# ADV7611.net
KiCad netlist of a schematic drawn in Altium Designer
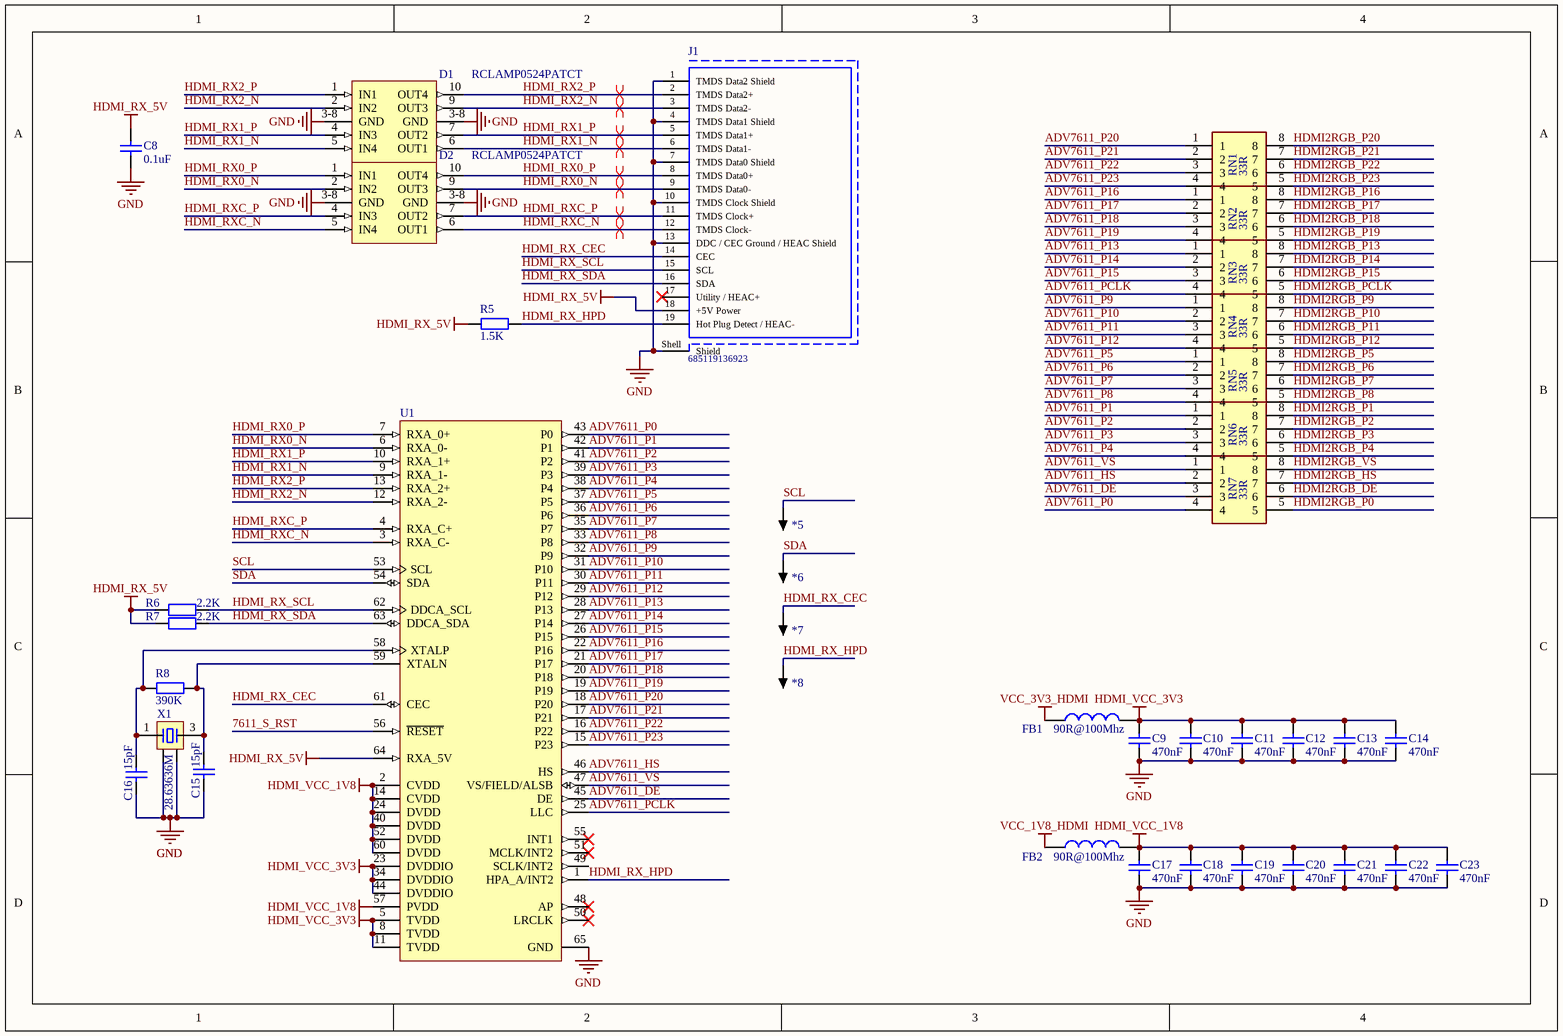
[diagram p0: ADV7611.SchDoc]

(export (version "E")
  (design (tool "Eeschema 10.0.6"))
  (components
    (comp (ref "*5")
      (value "CS")
      (footprint "R100")
      (description "探针焊盘")
      (libsource (lib "0.7 - 常用按键-开关-蜂鸣器-电池-测试点") (part "CS"))
    )
    (comp (ref "*6")
      (value "CS")
      (footprint "R100")
      (description "探针焊盘")
      (libsource (lib "0.7 - 常用按键-开关-蜂鸣器-电池-测试点") (part "CS"))
    )
    (comp (ref "*7")
      (value "CS")
      (footprint "R100")
      (description "探针焊盘")
      (libsource (lib "0.7 - 常用按键-开关-蜂鸣器-电池-测试点") (part "CS"))
    )
    (comp (ref "*8")
      (value "CS")
      (footprint "R100")
      (description "探针焊盘")
      (libsource (lib "0.7 - 常用按键-开关-蜂鸣器-电池-测试点") (part "CS"))
    )
    (comp (ref "C8")
      (value "0.1uF")
      (footprint "C0402_L")
      (description "贴片电容")
      (libsource (lib "0.1 - 电阻-电容-电感-磁珠-电位器") (part "C"))
    )
    (comp (ref "C9")
      (value "470nF")
      (footprint "C0402_L")
      (description "贴片电容")
      (libsource (lib "0.1 - 电阻-电容-电感-磁珠-电位器") (part "C"))
    )
    (comp (ref "C10")
      (value "470nF")
      (footprint "C0402_L")
      (description "贴片电容")
      (libsource (lib "0.1 - 电阻-电容-电感-磁珠-电位器") (part "C"))
    )
    (comp (ref "C11")
      (value "470nF")
      (footprint "C0402_L")
      (description "贴片电容")
      (libsource (lib "0.1 - 电阻-电容-电感-磁珠-电位器") (part "C"))
    )
    (comp (ref "C12")
      (value "470nF")
      (footprint "C0402_L")
      (description "贴片电容")
      (libsource (lib "0.1 - 电阻-电容-电感-磁珠-电位器") (part "C"))
    )
    (comp (ref "C13")
      (value "470nF")
      (footprint "C0402_L")
      (description "贴片电容")
      (libsource (lib "0.1 - 电阻-电容-电感-磁珠-电位器") (part "C"))
    )
    (comp (ref "C14")
      (value "470nF")
      (footprint "C0402_L")
      (description "贴片电容")
      (libsource (lib "0.1 - 电阻-电容-电感-磁珠-电位器") (part "C"))
    )
    (comp (ref "C15")
      (value "15pF")
      (footprint "C0402_L")
      (description "贴片电容")
      (libsource (lib "0.1 - 电阻-电容-电感-磁珠-电位器") (part "C"))
    )
    (comp (ref "C16")
      (value "15pF")
      (footprint "C0402_L")
      (description "贴片电容")
      (libsource (lib "0.1 - 电阻-电容-电感-磁珠-电位器") (part "C"))
    )
    (comp (ref "C17")
      (value "470nF")
      (footprint "C0402_L")
      (description "贴片电容")
      (libsource (lib "0.1 - 电阻-电容-电感-磁珠-电位器") (part "C"))
    )
    (comp (ref "C18")
      (value "470nF")
      (footprint "C0402_L")
      (description "贴片电容")
      (libsource (lib "0.1 - 电阻-电容-电感-磁珠-电位器") (part "C"))
    )
    (comp (ref "C19")
      (value "470nF")
      (footprint "C0402_L")
      (description "贴片电容")
      (libsource (lib "0.1 - 电阻-电容-电感-磁珠-电位器") (part "C"))
    )
    (comp (ref "C20")
      (value "470nF")
      (footprint "C0402_L")
      (description "贴片电容")
      (libsource (lib "0.1 - 电阻-电容-电感-磁珠-电位器") (part "C"))
    )
    (comp (ref "C21")
      (value "470nF")
      (footprint "C0402_L")
      (description "贴片电容")
      (libsource (lib "0.1 - 电阻-电容-电感-磁珠-电位器") (part "C"))
    )
    (comp (ref "C22")
      (value "470nF")
      (footprint "C0402_L")
      (description "贴片电容")
      (libsource (lib "0.1 - 电阻-电容-电感-磁珠-电位器") (part "C"))
    )
    (comp (ref "C23")
      (value "470nF")
      (footprint "C0402_L")
      (description "贴片电容")
      (libsource (lib "0.1 - 电阻-电容-电感-磁珠-电位器") (part "C"))
    )
    (comp (ref "D1")
      (value "RCLAMP0524PATCT")
      (footprint "FP-SLP2510P8-MFG")
      (description "TVS DIODE 5V 15V SLP2510P8")
      (libsource (lib "AD") (part "RCLAMP0524PATCT"))
    )
    (comp (ref "D2")
      (value "RCLAMP0524PATCT")
      (footprint "FP-SLP2510P8-MFG")
      (description "TVS DIODE 5V 15V SLP2510P8")
      (libsource (lib "AD") (part "RCLAMP0524PATCT"))
    )
    (comp (ref "FB1")
      (value "90R@100Mhz")
      (footprint "L0402")
      (description "磁珠")
      (libsource (lib "0.1 - 电阻-电容-电感-磁珠-电位器") (part "L"))
    )
    (comp (ref "FB2")
      (value "90R@100Mhz")
      (footprint "L0402")
      (description "磁珠")
      (libsource (lib "0.1 - 电阻-电容-电感-磁珠-电位器") (part "L"))
    )
    (comp (ref "J1")
      (value "685119136923")
      (footprint "685119136923")
      (description "Mini HDMI Type C Receptacle WR-COM, Horizontal, SMT")
      (fields (field (name "MANUFACTURER") "Wurth Elektronik") (field (name "PUBLISHER") "WurthElektronik"))
      (libsource (lib "Components - 25.06.23 - 21.10") (part "CMP-1502-00171-1"))
    )
    (comp (ref "R5")
      (value "1.5K")
      (footprint "R0402_L")
      (description "贴片电阻")
      (libsource (lib "0.1 - 电阻-电容-电感-磁珠-电位器") (part "R"))
    )
    (comp (ref "R6")
      (value "2.2K")
      (footprint "R0402_L")
      (description "贴片电阻")
      (libsource (lib "0.1 - 电阻-电容-电感-磁珠-电位器") (part "R"))
    )
    (comp (ref "R7")
      (value "2.2K")
      (footprint "R0402_L")
      (description "贴片电阻")
      (libsource (lib "0.1 - 电阻-电容-电感-磁珠-电位器") (part "R"))
    )
    (comp (ref "R8")
      (value "390K")
      (footprint "R0402_L")
      (description "贴片电阻")
      (libsource (lib "0.1 - 电阻-电容-电感-磁珠-电位器") (part "R"))
    )
    (comp (ref "RN1")
      (value "33R")
      (footprint "SamacSys:EXB28V510JX")
      (description "Resistor Network")
      (fields
        (field (name "MANUFACTURER_PART_NUMBER") "EXB-28V330JX")
        (field (name "MOUSER PART NUMBER") "667-EXB-28V330JX")
      )
      (libsource (lib "SamacSys") (part "0804"))
    )
    (comp (ref "RN2")
      (value "33R")
      (footprint "SamacSys:EXB28V510JX")
      (description "Resistor Network")
      (fields
        (field (name "MANUFACTURER_PART_NUMBER") "EXB-28V330JX")
        (field (name "MOUSER PART NUMBER") "667-EXB-28V330JX")
      )
      (libsource (lib "SamacSys") (part "0804"))
    )
    (comp (ref "RN3")
      (value "33R")
      (footprint "SamacSys:EXB28V510JX")
      (description "Resistor Network")
      (fields
        (field (name "MANUFACTURER_PART_NUMBER") "EXB-28V330JX")
        (field (name "MOUSER PART NUMBER") "667-EXB-28V330JX")
      )
      (libsource (lib "SamacSys") (part "0804"))
    )
    (comp (ref "RN4")
      (value "33R")
      (footprint "SamacSys:EXB28V510JX")
      (description "Resistor Network")
      (fields
        (field (name "MANUFACTURER_PART_NUMBER") "EXB-28V330JX")
        (field (name "MOUSER PART NUMBER") "667-EXB-28V330JX")
      )
      (libsource (lib "SamacSys") (part "0804"))
    )
    (comp (ref "RN5")
      (value "33R")
      (footprint "SamacSys:EXB28V510JX")
      (description "Resistor Network")
      (fields
        (field (name "MANUFACTURER_PART_NUMBER") "EXB-28V330JX")
        (field (name "MOUSER PART NUMBER") "667-EXB-28V330JX")
      )
      (libsource (lib "SamacSys") (part "0804"))
    )
    (comp (ref "RN6")
      (value "33R")
      (footprint "SamacSys:EXB28V510JX")
      (description "Resistor Network")
      (fields
        (field (name "MANUFACTURER_PART_NUMBER") "EXB-28V330JX")
        (field (name "MOUSER PART NUMBER") "667-EXB-28V330JX")
      )
      (libsource (lib "SamacSys") (part "0804"))
    )
    (comp (ref "RN7")
      (value "33R")
      (footprint "SamacSys:EXB28V510JX")
      (description "Resistor Network")
      (fields
        (field (name "MANUFACTURER_PART_NUMBER") "EXB-28V330JX")
        (field (name "MOUSER PART NUMBER") "667-EXB-28V330JX")
      )
      (libsource (lib "SamacSys") (part "0804"))
    )
    (comp (ref "U1")
      (value "~")
      (footprint "ADI-SW-64-2_L")
      (fields (field (name "MANUFACTURER") "Analog Devices") (field (name "PARTNUMBER") "ADV7611BSWZ-P"))
      (libsource (lib "Components - 25.06.23 - 21.52") (part "CMP-1517-00002-1"))
    )
    (comp (ref "X1")
      (value "28.63636M")
      (footprint "OSC 3225-4P")
      (description "4脚无源晶振")
      (libsource (lib "0.5 - 保险丝-晶振-光耦") (part "XTAL-4P"))
    )
  )
  (nets
    (net (code "1") (name "/7611_S_RST") (class "Default")
      (node (ref "U1") (pin "56") (pinfunction "~{RESET}_56") (pintype "input"))
    )
    (net (code "2") (name "/ADV7611_DE") (class "Default")
      (node (ref "RN7") (pin "3") (pinfunction "3_3") (pintype "passive"))
      (node (ref "U1") (pin "45") (pinfunction "DE_45") (pintype "output"))
    )
    (net (code "3") (name "/ADV7611_HS") (class "Default")
      (node (ref "RN7") (pin "2") (pinfunction "2_2") (pintype "passive"))
      (node (ref "U1") (pin "46") (pinfunction "HS_46") (pintype "output"))
    )
    (net (code "4") (name "/ADV7611_P0") (class "Default")
      (node (ref "RN7") (pin "4") (pinfunction "4_4") (pintype "passive"))
      (node (ref "U1") (pin "43") (pinfunction "P0_43") (pintype "output"))
    )
    (net (code "5") (name "/ADV7611_P1") (class "Default")
      (node (ref "RN6") (pin "1") (pinfunction "1_1") (pintype "passive"))
      (node (ref "U1") (pin "42") (pinfunction "P1_42") (pintype "output"))
    )
    (net (code "6") (name "/ADV7611_P2") (class "Default")
      (node (ref "RN6") (pin "2") (pinfunction "2_2") (pintype "passive"))
      (node (ref "U1") (pin "41") (pinfunction "P2_41") (pintype "output"))
    )
    (net (code "7") (name "/ADV7611_P3") (class "Default")
      (node (ref "RN6") (pin "3") (pinfunction "3_3") (pintype "passive"))
      (node (ref "U1") (pin "39") (pinfunction "P3_39") (pintype "output"))
    )
    (net (code "8") (name "/ADV7611_P4") (class "Default")
      (node (ref "RN6") (pin "4") (pinfunction "4_4") (pintype "passive"))
      (node (ref "U1") (pin "38") (pinfunction "P4_38") (pintype "output"))
    )
    (net (code "9") (name "/ADV7611_P5") (class "Default")
      (node (ref "RN5") (pin "1") (pinfunction "1_1") (pintype "passive"))
      (node (ref "U1") (pin "37") (pinfunction "P5_37") (pintype "output"))
    )
    (net (code "10") (name "/ADV7611_P6") (class "Default")
      (node (ref "RN5") (pin "2") (pinfunction "2_2") (pintype "passive"))
      (node (ref "U1") (pin "36") (pinfunction "P6_36") (pintype "output"))
    )
    (net (code "11") (name "/ADV7611_P7") (class "Default")
      (node (ref "RN5") (pin "3") (pinfunction "3_3") (pintype "passive"))
      (node (ref "U1") (pin "35") (pinfunction "P7_35") (pintype "output"))
    )
    (net (code "12") (name "/ADV7611_P8") (class "Default")
      (node (ref "RN5") (pin "4") (pinfunction "4_4") (pintype "passive"))
      (node (ref "U1") (pin "33") (pinfunction "P8_33") (pintype "output"))
    )
    (net (code "13") (name "/ADV7611_P9") (class "Default")
      (node (ref "RN4") (pin "1") (pinfunction "1_1") (pintype "passive"))
      (node (ref "U1") (pin "32") (pinfunction "P9_32") (pintype "output"))
    )
    (net (code "14") (name "/ADV7611_P10") (class "Default")
      (node (ref "RN4") (pin "2") (pinfunction "2_2") (pintype "passive"))
      (node (ref "U1") (pin "31") (pinfunction "P10_31") (pintype "output"))
    )
    (net (code "15") (name "/ADV7611_P11") (class "Default")
      (node (ref "RN4") (pin "3") (pinfunction "3_3") (pintype "passive"))
      (node (ref "U1") (pin "30") (pinfunction "P11_30") (pintype "output"))
    )
    (net (code "16") (name "/ADV7611_P12") (class "Default")
      (node (ref "RN4") (pin "4") (pinfunction "4_4") (pintype "passive"))
      (node (ref "U1") (pin "29") (pinfunction "P12_29") (pintype "output"))
    )
    (net (code "17") (name "/ADV7611_P13") (class "Default")
      (node (ref "RN3") (pin "1") (pinfunction "1_1") (pintype "passive"))
      (node (ref "U1") (pin "28") (pinfunction "P13_28") (pintype "output"))
    )
    (net (code "18") (name "/ADV7611_P14") (class "Default")
      (node (ref "RN3") (pin "2") (pinfunction "2_2") (pintype "passive"))
      (node (ref "U1") (pin "27") (pinfunction "P14_27") (pintype "output"))
    )
    (net (code "19") (name "/ADV7611_P15") (class "Default")
      (node (ref "RN3") (pin "3") (pinfunction "3_3") (pintype "passive"))
      (node (ref "U1") (pin "26") (pinfunction "P15_26") (pintype "output"))
    )
    (net (code "20") (name "/ADV7611_P16") (class "Default")
      (node (ref "RN2") (pin "1") (pinfunction "1_1") (pintype "passive"))
      (node (ref "U1") (pin "22") (pinfunction "P16_22") (pintype "output"))
    )
    (net (code "21") (name "/ADV7611_P17") (class "Default")
      (node (ref "RN2") (pin "2") (pinfunction "2_2") (pintype "passive"))
      (node (ref "U1") (pin "21") (pinfunction "P17_21") (pintype "output"))
    )
    (net (code "22") (name "/ADV7611_P18") (class "Default")
      (node (ref "RN2") (pin "3") (pinfunction "3_3") (pintype "passive"))
      (node (ref "U1") (pin "20") (pinfunction "P18_20") (pintype "output"))
    )
    (net (code "23") (name "/ADV7611_P19") (class "Default")
      (node (ref "RN2") (pin "4") (pinfunction "4_4") (pintype "passive"))
      (node (ref "U1") (pin "19") (pinfunction "P19_19") (pintype "output"))
    )
    (net (code "24") (name "/ADV7611_P20") (class "Default")
      (node (ref "RN1") (pin "1") (pinfunction "1_1") (pintype "passive"))
      (node (ref "U1") (pin "18") (pinfunction "P20_18") (pintype "output"))
    )
    (net (code "25") (name "/ADV7611_P21") (class "Default")
      (node (ref "RN1") (pin "2") (pinfunction "2_2") (pintype "passive"))
      (node (ref "U1") (pin "17") (pinfunction "P21_17") (pintype "output"))
    )
    (net (code "26") (name "/ADV7611_P22") (class "Default")
      (node (ref "RN1") (pin "3") (pinfunction "3_3") (pintype "passive"))
      (node (ref "U1") (pin "16") (pinfunction "P22_16") (pintype "output"))
    )
    (net (code "27") (name "/ADV7611_P23") (class "Default")
      (node (ref "RN1") (pin "4") (pinfunction "4_4") (pintype "passive"))
      (node (ref "U1") (pin "15") (pinfunction "P23_15") (pintype "output"))
    )
    (net (code "28") (name "/ADV7611_PCLK") (class "Default")
      (node (ref "RN3") (pin "4") (pinfunction "4_4") (pintype "passive"))
      (node (ref "U1") (pin "25") (pinfunction "LLC_25") (pintype "output"))
    )
    (net (code "29") (name "/ADV7611_VS") (class "Default")
      (node (ref "RN7") (pin "1") (pinfunction "1_1") (pintype "passive"))
      (node (ref "U1") (pin "47") (pinfunction "VS/FIELD/ALSB_47") (pintype "bidirectional"))
    )
    (net (code "30") (name "/HDMI2RGB_DE") (class "Default")
      (node (ref "RN7") (pin "6") (pinfunction "6_6") (pintype "passive"))
    )
    (net (code "31") (name "/HDMI2RGB_HS") (class "Default")
      (node (ref "RN7") (pin "7") (pinfunction "7_7") (pintype "passive"))
    )
    (net (code "32") (name "/HDMI2RGB_P0") (class "Default")
      (node (ref "RN7") (pin "5") (pinfunction "5_5") (pintype "passive"))
    )
    (net (code "33") (name "/HDMI2RGB_P1") (class "Default")
      (node (ref "RN6") (pin "8") (pinfunction "8_8") (pintype "passive"))
    )
    (net (code "34") (name "/HDMI2RGB_P2") (class "Default")
      (node (ref "RN6") (pin "7") (pinfunction "7_7") (pintype "passive"))
    )
    (net (code "35") (name "/HDMI2RGB_P3") (class "Default")
      (node (ref "RN6") (pin "6") (pinfunction "6_6") (pintype "passive"))
    )
    (net (code "36") (name "/HDMI2RGB_P4") (class "Default")
      (node (ref "RN6") (pin "5") (pinfunction "5_5") (pintype "passive"))
    )
    (net (code "37") (name "/HDMI2RGB_P5") (class "Default")
      (node (ref "RN5") (pin "8") (pinfunction "8_8") (pintype "passive"))
    )
    (net (code "38") (name "/HDMI2RGB_P6") (class "Default")
      (node (ref "RN5") (pin "7") (pinfunction "7_7") (pintype "passive"))
    )
    (net (code "39") (name "/HDMI2RGB_P7") (class "Default")
      (node (ref "RN5") (pin "6") (pinfunction "6_6") (pintype "passive"))
    )
    (net (code "40") (name "/HDMI2RGB_P8") (class "Default")
      (node (ref "RN5") (pin "5") (pinfunction "5_5") (pintype "passive"))
    )
    (net (code "41") (name "/HDMI2RGB_P9") (class "Default")
      (node (ref "RN4") (pin "8") (pinfunction "8_8") (pintype "passive"))
    )
    (net (code "42") (name "/HDMI2RGB_P10") (class "Default")
      (node (ref "RN4") (pin "7") (pinfunction "7_7") (pintype "passive"))
    )
    (net (code "43") (name "/HDMI2RGB_P11") (class "Default")
      (node (ref "RN4") (pin "6") (pinfunction "6_6") (pintype "passive"))
    )
    (net (code "44") (name "/HDMI2RGB_P12") (class "Default")
      (node (ref "RN4") (pin "5") (pinfunction "5_5") (pintype "passive"))
    )
    (net (code "45") (name "/HDMI2RGB_P13") (class "Default")
      (node (ref "RN3") (pin "8") (pinfunction "8_8") (pintype "passive"))
    )
    (net (code "46") (name "/HDMI2RGB_P14") (class "Default")
      (node (ref "RN3") (pin "7") (pinfunction "7_7") (pintype "passive"))
    )
    (net (code "47") (name "/HDMI2RGB_P15") (class "Default")
      (node (ref "RN3") (pin "6") (pinfunction "6_6") (pintype "passive"))
    )
    (net (code "48") (name "/HDMI2RGB_P16") (class "Default")
      (node (ref "RN2") (pin "8") (pinfunction "8_8") (pintype "passive"))
    )
    (net (code "49") (name "/HDMI2RGB_P17") (class "Default")
      (node (ref "RN2") (pin "7") (pinfunction "7_7") (pintype "passive"))
    )
    (net (code "50") (name "/HDMI2RGB_P18") (class "Default")
      (node (ref "RN2") (pin "6") (pinfunction "6_6") (pintype "passive"))
    )
    (net (code "51") (name "/HDMI2RGB_P19") (class "Default")
      (node (ref "RN2") (pin "5") (pinfunction "5_5") (pintype "passive"))
    )
    (net (code "52") (name "/HDMI2RGB_P20") (class "Default")
      (node (ref "RN1") (pin "8") (pinfunction "8_8") (pintype "passive"))
    )
    (net (code "53") (name "/HDMI2RGB_P21") (class "Default")
      (node (ref "RN1") (pin "7") (pinfunction "7_7") (pintype "passive"))
    )
    (net (code "54") (name "/HDMI2RGB_P22") (class "Default")
      (node (ref "RN1") (pin "6") (pinfunction "6_6") (pintype "passive"))
    )
    (net (code "55") (name "/HDMI2RGB_P23") (class "Default")
      (node (ref "RN1") (pin "5") (pinfunction "5_5") (pintype "passive"))
    )
    (net (code "56") (name "/HDMI2RGB_PCLK") (class "Default")
      (node (ref "RN3") (pin "5") (pinfunction "5_5") (pintype "passive"))
    )
    (net (code "57") (name "/HDMI2RGB_VS") (class "Default")
      (node (ref "RN7") (pin "8") (pinfunction "8_8") (pintype "passive"))
    )
    (net (code "58") (name "/HDMI_RX0_N") (class "Default")
      (node (ref "D2") (pin "2") (pinfunction "IN2_2") (pintype "input"))
      (node (ref "D2") (pin "9") (pinfunction "OUT3_9") (pintype "output"))
      (node (ref "J1") (pin "9") (pinfunction "TMDS_Data0-_9") (pintype "passive"))
      (node (ref "U1") (pin "6") (pinfunction "RXA_0-_6") (pintype "input"))
    )
    (net (code "59") (name "/HDMI_RX0_P") (class "Default")
      (node (ref "D2") (pin "1") (pinfunction "IN1_1") (pintype "input"))
      (node (ref "D2") (pin "10") (pinfunction "OUT4_10") (pintype "output"))
      (node (ref "J1") (pin "8") (pinfunction "TMDS_Data0+_8") (pintype "passive"))
      (node (ref "U1") (pin "7") (pinfunction "RXA_0+_7") (pintype "input"))
    )
    (net (code "60") (name "/HDMI_RX1_N") (class "Default")
      (node (ref "D1") (pin "5") (pinfunction "IN4_5") (pintype "input"))
      (node (ref "D1") (pin "6") (pinfunction "OUT1_6") (pintype "output"))
      (node (ref "J1") (pin "6") (pinfunction "TMDS_Data1-_6") (pintype "passive"))
      (node (ref "U1") (pin "9") (pinfunction "RXA_1-_9") (pintype "input"))
    )
    (net (code "61") (name "/HDMI_RX1_P") (class "Default")
      (node (ref "D1") (pin "4") (pinfunction "IN3_4") (pintype "input"))
      (node (ref "D1") (pin "7") (pinfunction "OUT2_7") (pintype "output"))
      (node (ref "J1") (pin "5") (pinfunction "TMDS_Data1+_5") (pintype "passive"))
      (node (ref "U1") (pin "10") (pinfunction "RXA_1+_10") (pintype "input"))
    )
    (net (code "62") (name "/HDMI_RX2_N") (class "Default")
      (node (ref "D1") (pin "2") (pinfunction "IN2_2") (pintype "input"))
      (node (ref "D1") (pin "9") (pinfunction "OUT3_9") (pintype "output"))
      (node (ref "J1") (pin "3") (pinfunction "TMDS_Data2-_3") (pintype "passive"))
      (node (ref "U1") (pin "12") (pinfunction "RXA_2-_12") (pintype "input"))
    )
    (net (code "63") (name "/HDMI_RX2_P") (class "Default")
      (node (ref "D1") (pin "1") (pinfunction "IN1_1") (pintype "input"))
      (node (ref "D1") (pin "10") (pinfunction "OUT4_10") (pintype "output"))
      (node (ref "J1") (pin "2") (pinfunction "TMDS_Data2+_2") (pintype "passive"))
      (node (ref "U1") (pin "13") (pinfunction "RXA_2+_13") (pintype "input"))
    )
    (net (code "64") (name "/HDMI_RXC_N") (class "Default")
      (node (ref "D2") (pin "5") (pinfunction "IN4_5") (pintype "input"))
      (node (ref "D2") (pin "6") (pinfunction "OUT1_6") (pintype "output"))
      (node (ref "J1") (pin "12") (pinfunction "TMDS_Clock-_12") (pintype "passive"))
      (node (ref "U1") (pin "3") (pinfunction "RXA_C-_3") (pintype "input"))
    )
    (net (code "65") (name "/HDMI_RXC_P") (class "Default")
      (node (ref "D2") (pin "4") (pinfunction "IN3_4") (pintype "input"))
      (node (ref "D2") (pin "7") (pinfunction "OUT2_7") (pintype "output"))
      (node (ref "J1") (pin "11") (pinfunction "TMDS_Clock+_11") (pintype "passive"))
      (node (ref "U1") (pin "4") (pinfunction "RXA_C+_4") (pintype "input"))
    )
    (net (code "66") (name "/HDMI_RX_CEC") (class "Default")
      (node (ref "*7") (pin "1") (pinfunction "1_1") (pintype "passive"))
      (node (ref "J1") (pin "14") (pinfunction "CEC_14") (pintype "passive"))
      (node (ref "U1") (pin "61") (pinfunction "CEC_61") (pintype "bidirectional"))
    )
    (net (code "67") (name "/HDMI_RX_HPD") (class "Default")
      (node (ref "*8") (pin "1") (pinfunction "1_1") (pintype "passive"))
      (node (ref "J1") (pin "19") (pinfunction "Hot_Plug_Detect_/_HEAC-_19") (pintype "passive"))
      (node (ref "R5") (pin "1") (pinfunction "1_1") (pintype "passive"))
      (node (ref "U1") (pin "1") (pinfunction "HPA_A/INT2_1") (pintype "output"))
    )
    (net (code "68") (name "/HDMI_RX_SCL") (class "Default")
      (node (ref "J1") (pin "15") (pinfunction "SCL_15") (pintype "passive"))
      (node (ref "R6") (pin "1") (pinfunction "1_1") (pintype "passive"))
      (node (ref "U1") (pin "62") (pinfunction "DDCA_SCL_62") (pintype "input"))
    )
    (net (code "69") (name "/HDMI_RX_SDA") (class "Default")
      (node (ref "J1") (pin "16") (pinfunction "SDA_16") (pintype "passive"))
      (node (ref "R7") (pin "1") (pinfunction "1_1") (pintype "passive"))
      (node (ref "U1") (pin "63") (pinfunction "DDCA_SDA_63") (pintype "bidirectional"))
    )
    (net (code "70") (name "/SCL") (class "Default")
      (node (ref "*5") (pin "1") (pinfunction "1_1") (pintype "passive"))
      (node (ref "U1") (pin "53") (pinfunction "SCL_53") (pintype "input"))
    )
    (net (code "71") (name "/SDA") (class "Default")
      (node (ref "*6") (pin "1") (pinfunction "1_1") (pintype "passive"))
      (node (ref "U1") (pin "54") (pinfunction "SDA_54") (pintype "bidirectional"))
    )
    (net (code "72") (name "GND") (class "Default")
      (node (ref "C10") (pin "1") (pinfunction "1_1") (pintype "passive"))
      (node (ref "C11") (pin "1") (pinfunction "1_1") (pintype "passive"))
      (node (ref "C12") (pin "1") (pinfunction "1_1") (pintype "passive"))
      (node (ref "C13") (pin "1") (pinfunction "1_1") (pintype "passive"))
      (node (ref "C14") (pin "1") (pinfunction "1_1") (pintype "passive"))
      (node (ref "C15") (pin "2") (pinfunction "2_2") (pintype "passive"))
      (node (ref "C16") (pin "2") (pinfunction "2_2") (pintype "passive"))
      (node (ref "C17") (pin "1") (pinfunction "1_1") (pintype "passive"))
      (node (ref "C18") (pin "1") (pinfunction "1_1") (pintype "passive"))
      (node (ref "C19") (pin "1") (pinfunction "1_1") (pintype "passive"))
      (node (ref "C20") (pin "1") (pinfunction "1_1") (pintype "passive"))
      (node (ref "C21") (pin "1") (pinfunction "1_1") (pintype "passive"))
      (node (ref "C22") (pin "1") (pinfunction "1_1") (pintype "passive"))
      (node (ref "C23") (pin "1") (pinfunction "1_1") (pintype "passive"))
      (node (ref "C8") (pin "1") (pinfunction "1_1") (pintype "passive"))
      (node (ref "C9") (pin "1") (pinfunction "1_1") (pintype "passive"))
      (node (ref "D1") (pin "3-8") (pinfunction "GND_3-8") (pintype "tri_state"))
      (node (ref "D2") (pin "3-8") (pinfunction "GND_3-8") (pintype "tri_state"))
      (node (ref "J1") (pin "1") (pinfunction "TMDS_Data2_Shield_1") (pintype "passive"))
      (node (ref "J1") (pin "10") (pinfunction "TMDS_Clock_Shield_10") (pintype "passive"))
      (node (ref "J1") (pin "13") (pinfunction "DDC_/_CEC_Ground_/_HEAC_Shield_13") (pintype "passive"))
      (node (ref "J1") (pin "4") (pinfunction "TMDS_Data1_Shield_4") (pintype "passive"))
      (node (ref "J1") (pin "7") (pinfunction "TMDS_Data0_Shield_7") (pintype "passive"))
      (node (ref "J1") (pin "Shell") (pinfunction "Shield_Shell") (pintype "passive"))
      (node (ref "U1") (pin "65") (pinfunction "GND_65") (pintype "power_in"))
      (node (ref "X1") (pin "2") (pinfunction "2_2") (pintype "passive"))
      (node (ref "X1") (pin "4") (pinfunction "4_4") (pintype "passive"))
    )
    (net (code "73") (name "HDMI_RX_5V") (class "Default")
      (node (ref "C8") (pin "2") (pinfunction "2_2") (pintype "passive"))
      (node (ref "J1") (pin "18") (pinfunction "+5V_Power_18") (pintype "passive"))
      (node (ref "R5") (pin "2") (pinfunction "2_2") (pintype "passive"))
      (node (ref "R6") (pin "2") (pinfunction "2_2") (pintype "passive"))
      (node (ref "R7") (pin "2") (pinfunction "2_2") (pintype "passive"))
      (node (ref "U1") (pin "64") (pinfunction "RXA_5V_64") (pintype "input"))
    )
    (net (code "74") (name "HDMI_VCC_1V8") (class "Default")
      (node (ref "C17") (pin "2") (pinfunction "2_2") (pintype "passive"))
      (node (ref "C18") (pin "2") (pinfunction "2_2") (pintype "passive"))
      (node (ref "C19") (pin "2") (pinfunction "2_2") (pintype "passive"))
      (node (ref "C20") (pin "2") (pinfunction "2_2") (pintype "passive"))
      (node (ref "C21") (pin "2") (pinfunction "2_2") (pintype "passive"))
      (node (ref "C22") (pin "2") (pinfunction "2_2") (pintype "passive"))
      (node (ref "C23") (pin "2") (pinfunction "2_2") (pintype "passive"))
      (node (ref "FB2") (pin "2") (pinfunction "2_2") (pintype "passive"))
      (node (ref "U1") (pin "14") (pinfunction "CVDD_14") (pintype "power_in"))
      (node (ref "U1") (pin "2") (pinfunction "CVDD_2") (pintype "power_in"))
      (node (ref "U1") (pin "24") (pinfunction "DVDD_24") (pintype "power_in"))
      (node (ref "U1") (pin "40") (pinfunction "DVDD_40") (pintype "power_in"))
      (node (ref "U1") (pin "52") (pinfunction "DVDD_52") (pintype "power_in"))
      (node (ref "U1") (pin "57") (pinfunction "PVDD_57") (pintype "power_in"))
      (node (ref "U1") (pin "60") (pinfunction "DVDD_60") (pintype "power_in"))
    )
    (net (code "75") (name "HDMI_VCC_3V3") (class "Default")
      (node (ref "C10") (pin "2") (pinfunction "2_2") (pintype "passive"))
      (node (ref "C11") (pin "2") (pinfunction "2_2") (pintype "passive"))
      (node (ref "C12") (pin "2") (pinfunction "2_2") (pintype "passive"))
      (node (ref "C13") (pin "2") (pinfunction "2_2") (pintype "passive"))
      (node (ref "C14") (pin "2") (pinfunction "2_2") (pintype "passive"))
      (node (ref "C9") (pin "2") (pinfunction "2_2") (pintype "passive"))
      (node (ref "FB1") (pin "2") (pinfunction "2_2") (pintype "passive"))
      (node (ref "U1") (pin "11") (pinfunction "TVDD_11") (pintype "power_in"))
      (node (ref "U1") (pin "23") (pinfunction "DVDDIO_23") (pintype "power_in"))
      (node (ref "U1") (pin "34") (pinfunction "DVDDIO_34") (pintype "power_in"))
      (node (ref "U1") (pin "44") (pinfunction "DVDDIO_44") (pintype "power_in"))
      (node (ref "U1") (pin "5") (pinfunction "TVDD_5") (pintype "power_in"))
      (node (ref "U1") (pin "8") (pinfunction "TVDD_8") (pintype "power_in"))
    )
    (net (code "76") (name "Net-(U1-XTALN)") (class "Default")
      (node (ref "C15") (pin "1") (pinfunction "1_1") (pintype "passive"))
      (node (ref "R8") (pin "2") (pinfunction "2_2") (pintype "passive"))
      (node (ref "U1") (pin "59") (pinfunction "XTALN_59") (pintype "passive"))
      (node (ref "X1") (pin "3") (pinfunction "3_3") (pintype "passive"))
    )
    (net (code "77") (name "Net-(U1-XTALP)") (class "Default")
      (node (ref "C16") (pin "1") (pinfunction "1_1") (pintype "passive"))
      (node (ref "R8") (pin "1") (pinfunction "1_1") (pintype "passive"))
      (node (ref "U1") (pin "58") (pinfunction "XTALP_58") (pintype "input"))
      (node (ref "X1") (pin "1") (pinfunction "1_1") (pintype "passive"))
    )
    (net (code "78") (name "VCC_1V8_HDMI") (class "Default")
      (node (ref "FB2") (pin "1") (pinfunction "1_1") (pintype "passive"))
    )
    (net (code "79") (name "VCC_3V3_HDMI") (class "Default")
      (node (ref "FB1") (pin "1") (pinfunction "1_1") (pintype "passive"))
    )
    (net (code "80") (name "unconnected-(J1-Utility_{slash}_HEAC+-Pad17)") (class "Default")
      (node (ref "J1") (pin "17") (pinfunction "Utility_/_HEAC+_17") (pintype "passive+no_connect"))
    )
    (net (code "81") (name "unconnected-(U1-AP-Pad48)") (class "Default")
      (node (ref "U1") (pin "48") (pinfunction "AP_48") (pintype "output+no_connect"))
    )
    (net (code "82") (name "unconnected-(U1-INT1-Pad55)") (class "Default")
      (node (ref "U1") (pin "55") (pinfunction "INT1_55") (pintype "output+no_connect"))
    )
    (net (code "83") (name "unconnected-(U1-LRCLK-Pad50)") (class "Default")
      (node (ref "U1") (pin "50") (pinfunction "LRCLK_50") (pintype "output+no_connect"))
    )
    (net (code "84") (name "unconnected-(U1-MCLK{slash}INT2-Pad51)") (class "Default")
      (node (ref "U1") (pin "51") (pinfunction "MCLK/INT2_51") (pintype "output+no_connect"))
    )
    (net (code "85") (name "unconnected-(U1-SCLK{slash}INT2-Pad49)") (class "Default")
      (node (ref "U1") (pin "49") (pinfunction "SCLK/INT2_49") (pintype "output"))
    )
  )
)
